# rhex.net
KiCad netlist of a schematic drawn in EAGLE
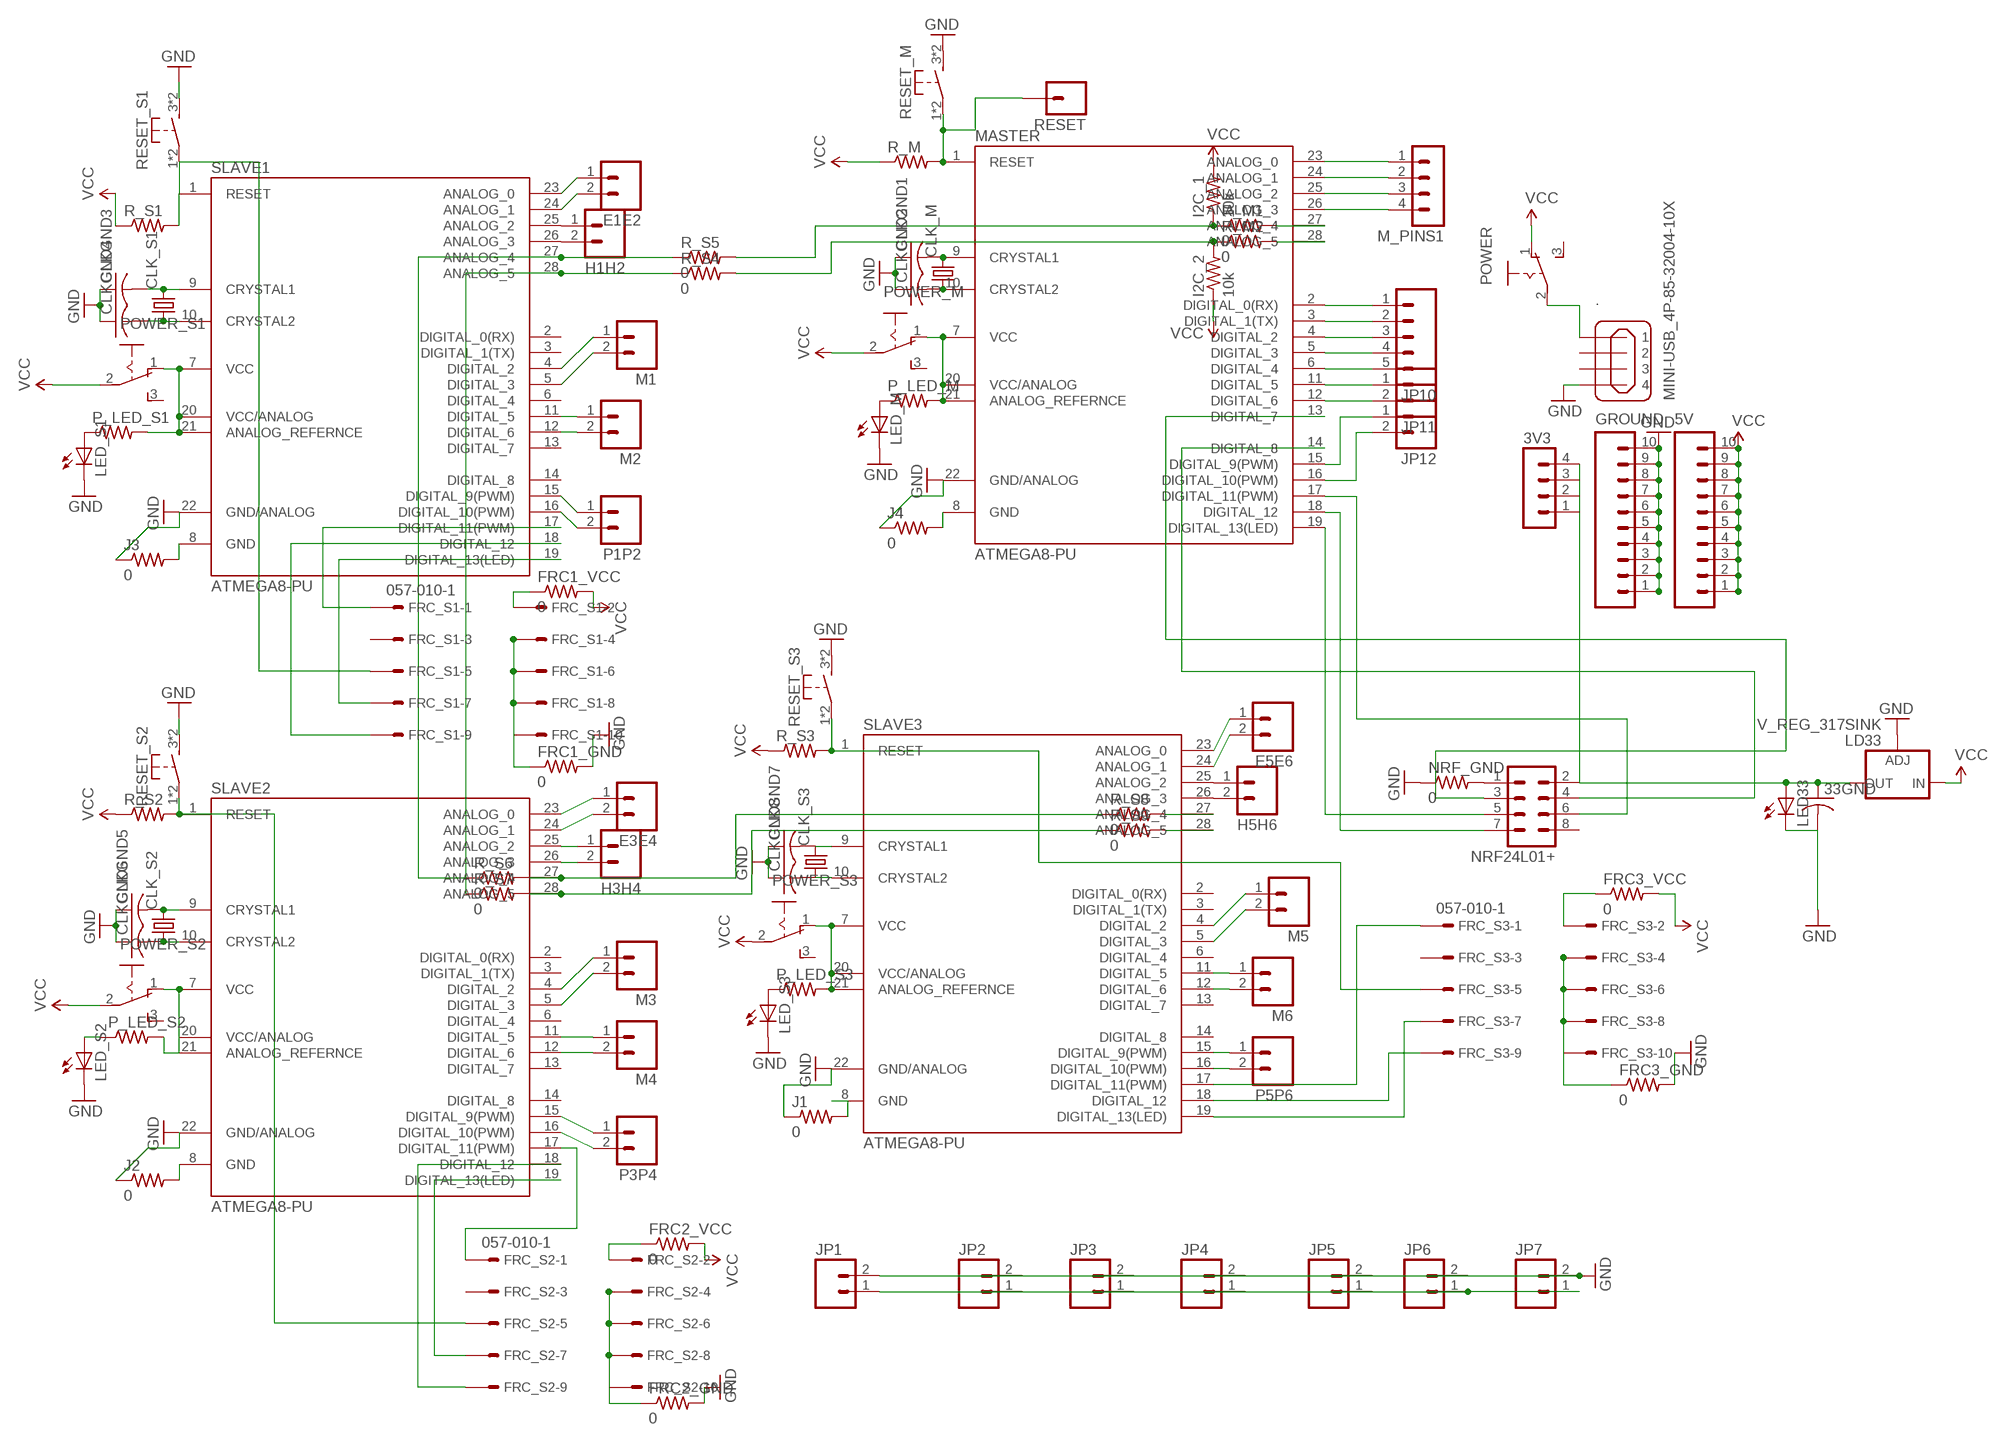
[diagram p0: schematic, sheet 1]

(export (version "E")
  (design (tool "Eeschema 10.0.6"))
  (components
    (comp (ref ".")
      (value "MINI-USB_4P-85-32004-10X")
      (footprint "eagle-import:85-32004-10X")
      (libsource (lib "eagle-import") (part "MINI-USB_4P-85-32004-10X"))
    )
    (comp (ref "3V3")
      (value "MA04-1")
      (footprint "eagle-import:MA04-1")
      (libsource (lib "eagle-import") (part "MA04-1"))
    )
    (comp (ref "5V")
      (value "M10SILK_FEMALE_PTH")
      (footprint "eagle-import:1X10")
      (libsource (lib "eagle-import") (part "M10SILK_FEMALE_PTH"))
    )
    (comp (ref "33GND")
      (value "C-US050-024X044")
      (footprint "eagle-import:C050-024X044")
      (libsource (lib "eagle-import") (part "C-US050-024X044"))
    )
    (comp (ref "CLKGND1")
      (value "C-US050-024X044")
      (footprint "eagle-import:C050-024X044")
      (libsource (lib "eagle-import") (part "C-US050-024X044"))
    )
    (comp (ref "CLKGND2")
      (value "C-US050-024X044")
      (footprint "eagle-import:C050-024X044")
      (libsource (lib "eagle-import") (part "C-US050-024X044"))
    )
    (comp (ref "CLKGND3")
      (value "C-US050-024X044")
      (footprint "eagle-import:C050-024X044")
      (libsource (lib "eagle-import") (part "C-US050-024X044"))
    )
    (comp (ref "CLKGND4")
      (value "C-US050-024X044")
      (footprint "eagle-import:C050-024X044")
      (libsource (lib "eagle-import") (part "C-US050-024X044"))
    )
    (comp (ref "CLKGND5")
      (value "C-US050-024X044")
      (footprint "eagle-import:C050-024X044")
      (libsource (lib "eagle-import") (part "C-US050-024X044"))
    )
    (comp (ref "CLKGND6")
      (value "C-US050-024X044")
      (footprint "eagle-import:C050-024X044")
      (libsource (lib "eagle-import") (part "C-US050-024X044"))
    )
    (comp (ref "CLKGND7")
      (value "C-US050-024X044")
      (footprint "eagle-import:C050-024X044")
      (libsource (lib "eagle-import") (part "C-US050-024X044"))
    )
    (comp (ref "CLKGND8")
      (value "C-US050-024X044")
      (footprint "eagle-import:C050-024X044")
      (libsource (lib "eagle-import") (part "C-US050-024X044"))
    )
    (comp (ref "CLK_M")
      (value "CRYSTALHC49U-V")
      (footprint "eagle-import:HC49U-V")
      (libsource (lib "eagle-import") (part "CRYSTALHC49U-V"))
    )
    (comp (ref "CLK_S1")
      (value "CRYSTALHC49U-V")
      (footprint "eagle-import:HC49U-V")
      (libsource (lib "eagle-import") (part "CRYSTALHC49U-V"))
    )
    (comp (ref "CLK_S2")
      (value "CRYSTALHC49U-V")
      (footprint "eagle-import:HC49U-V")
      (libsource (lib "eagle-import") (part "CRYSTALHC49U-V"))
    )
    (comp (ref "CLK_S3")
      (value "CRYSTALHC49U-V")
      (footprint "eagle-import:HC49U-V")
      (libsource (lib "eagle-import") (part "CRYSTALHC49U-V"))
    )
    (comp (ref "E1E2")
      (value "M02LOCK")
      (footprint "eagle-import:1X02_LOCK")
      (libsource (lib "eagle-import") (part "M02LOCK"))
    )
    (comp (ref "E3E4")
      (value "M02LOCK")
      (footprint "eagle-import:1X02_LOCK")
      (libsource (lib "eagle-import") (part "M02LOCK"))
    )
    (comp (ref "E5E6")
      (value "M02LOCK")
      (footprint "eagle-import:1X02_LOCK")
      (libsource (lib "eagle-import") (part "M02LOCK"))
    )
    (comp (ref "FRC1_GND")
      (value "0")
      (footprint "eagle-import:0411_15")
      (libsource (lib "eagle-import") (part "R-US_0411/15"))
    )
    (comp (ref "FRC1_VCC")
      (value "0")
      (footprint "eagle-import:0411_15")
      (libsource (lib "eagle-import") (part "R-US_0411/15"))
    )
    (comp (ref "FRC2_GND")
      (value "0")
      (footprint "eagle-import:0411_15")
      (libsource (lib "eagle-import") (part "R-US_0411/15"))
    )
    (comp (ref "FRC2_VCC")
      (value "0")
      (footprint "eagle-import:0411_15")
      (libsource (lib "eagle-import") (part "R-US_0411/15"))
    )
    (comp (ref "FRC3_GND")
      (value "0")
      (footprint "eagle-import:0411_15")
      (libsource (lib "eagle-import") (part "R-US_0411/15"))
    )
    (comp (ref "FRC3_VCC")
      (value "0")
      (footprint "eagle-import:0411_15")
      (libsource (lib "eagle-import") (part "R-US_0411/15"))
    )
    (comp (ref "FRC_S1")
      (value "057-010-1")
      (footprint "eagle-import:057-010-1")
      (libsource (lib "eagle-import") (part "057-010-1"))
    )
    (comp (ref "FRC_S2")
      (value "057-010-1")
      (footprint "eagle-import:057-010-1")
      (libsource (lib "eagle-import") (part "057-010-1"))
    )
    (comp (ref "FRC_S3")
      (value "057-010-1")
      (footprint "eagle-import:057-010-1")
      (libsource (lib "eagle-import") (part "057-010-1"))
    )
    (comp (ref "GROUND")
      (value "M10SILK_FEMALE_PTH")
      (footprint "eagle-import:1X10")
      (libsource (lib "eagle-import") (part "M10SILK_FEMALE_PTH"))
    )
    (comp (ref "H1H2")
      (value "M02LOCK")
      (footprint "eagle-import:1X02_LOCK")
      (libsource (lib "eagle-import") (part "M02LOCK"))
    )
    (comp (ref "H3H4")
      (value "M02LOCK")
      (footprint "eagle-import:1X02_LOCK")
      (libsource (lib "eagle-import") (part "M02LOCK"))
    )
    (comp (ref "H5H6")
      (value "M02LOCK")
      (footprint "eagle-import:1X02_LOCK")
      (libsource (lib "eagle-import") (part "M02LOCK"))
    )
    (comp (ref "I2C_1")
      (value "10k")
      (footprint "eagle-import:0411_15")
      (libsource (lib "eagle-import") (part "R-US_0411/15"))
    )
    (comp (ref "I2C_2")
      (value "10k")
      (footprint "eagle-import:0411_15")
      (libsource (lib "eagle-import") (part "R-US_0411/15"))
    )
    (comp (ref "J1")
      (value "0")
      (footprint "eagle-import:0411_15")
      (libsource (lib "eagle-import") (part "R-US_0411/15"))
    )
    (comp (ref "J2")
      (value "0")
      (footprint "eagle-import:0411_15")
      (libsource (lib "eagle-import") (part "R-US_0411/15"))
    )
    (comp (ref "J3")
      (value "0")
      (footprint "eagle-import:0411_15")
      (libsource (lib "eagle-import") (part "R-US_0411/15"))
    )
    (comp (ref "J4")
      (value "0")
      (footprint "eagle-import:0411_15")
      (libsource (lib "eagle-import") (part "R-US_0411/15"))
    )
    (comp (ref "JP1")
      (value "M023.5MM")
      (footprint "eagle-import:SCREWTERMINAL-3.5MM-2")
      (libsource (lib "eagle-import") (part "M023.5MM"))
    )
    (comp (ref "JP2")
      (value "M023.5MM")
      (footprint "eagle-import:SCREWTERMINAL-3.5MM-2")
      (libsource (lib "eagle-import") (part "M023.5MM"))
    )
    (comp (ref "JP3")
      (value "M023.5MM")
      (footprint "eagle-import:SCREWTERMINAL-3.5MM-2")
      (libsource (lib "eagle-import") (part "M023.5MM"))
    )
    (comp (ref "JP4")
      (value "M023.5MM")
      (footprint "eagle-import:SCREWTERMINAL-3.5MM-2")
      (libsource (lib "eagle-import") (part "M023.5MM"))
    )
    (comp (ref "JP5")
      (value "M023.5MM")
      (footprint "eagle-import:SCREWTERMINAL-3.5MM-2")
      (libsource (lib "eagle-import") (part "M023.5MM"))
    )
    (comp (ref "JP6")
      (value "M023.5MM")
      (footprint "eagle-import:SCREWTERMINAL-3.5MM-2")
      (libsource (lib "eagle-import") (part "M023.5MM"))
    )
    (comp (ref "JP7")
      (value "M023.5MM")
      (footprint "eagle-import:SCREWTERMINAL-3.5MM-2")
      (libsource (lib "eagle-import") (part "M023.5MM"))
    )
    (comp (ref "JP10")
      (value "M05PTH")
      (footprint "eagle-import:1X05")
      (libsource (lib "eagle-import") (part "M05PTH"))
    )
    (comp (ref "JP11")
      (value "M02PTH")
      (footprint "eagle-import:1X02")
      (libsource (lib "eagle-import") (part "M02PTH"))
    )
    (comp (ref "JP12")
      (value "M02PTH")
      (footprint "eagle-import:1X02")
      (libsource (lib "eagle-import") (part "M02PTH"))
    )
    (comp (ref "LD33")
      (value "V_REG_317SINK")
      (footprint "eagle-import:TO220-ADJ")
      (libsource (lib "eagle-import") (part "V_REG_317SINK"))
    )
    (comp (ref "LED33")
      (value "LED3MM")
      (footprint "eagle-import:LED3MM")
      (libsource (lib "eagle-import") (part "LED3MM"))
    )
    (comp (ref "LED_M")
      (value "LED3MM")
      (footprint "eagle-import:LED3MM")
      (libsource (lib "eagle-import") (part "led_LED3MM"))
    )
    (comp (ref "LED_S1")
      (value "LED3MM")
      (footprint "eagle-import:LED3MM")
      (libsource (lib "eagle-import") (part "led_LED3MM"))
    )
    (comp (ref "LED_S2")
      (value "LED3MM")
      (footprint "eagle-import:LED3MM")
      (libsource (lib "eagle-import") (part "led_LED3MM"))
    )
    (comp (ref "LED_S3")
      (value "LED3MM")
      (footprint "eagle-import:LED3MM")
      (libsource (lib "eagle-import") (part "led_LED3MM"))
    )
    (comp (ref "M1")
      (value "M02LOCK")
      (footprint "eagle-import:1X02_LOCK")
      (libsource (lib "eagle-import") (part "M02LOCK"))
    )
    (comp (ref "M2")
      (value "M02LOCK")
      (footprint "eagle-import:1X02_LOCK")
      (libsource (lib "eagle-import") (part "M02LOCK"))
    )
    (comp (ref "M3")
      (value "M02LOCK")
      (footprint "eagle-import:1X02_LOCK")
      (libsource (lib "eagle-import") (part "M02LOCK"))
    )
    (comp (ref "M4")
      (value "M02LOCK")
      (footprint "eagle-import:1X02_LOCK")
      (libsource (lib "eagle-import") (part "M02LOCK"))
    )
    (comp (ref "M5")
      (value "M02LOCK")
      (footprint "eagle-import:1X02_LOCK")
      (libsource (lib "eagle-import") (part "M02LOCK"))
    )
    (comp (ref "M6")
      (value "M02LOCK")
      (footprint "eagle-import:1X02_LOCK")
      (libsource (lib "eagle-import") (part "M02LOCK"))
    )
    (comp (ref "MASTER")
      (value "ATMEGA8-PU")
      (footprint "eagle-import:DIL28-3")
      (libsource (lib "eagle-import") (part "ATMEGA8-PU"))
    )
    (comp (ref "M_PINS1")
      (value "MA04-1")
      (footprint "eagle-import:MA04-1")
      (libsource (lib "eagle-import") (part "MA04-1"))
    )
    (comp (ref "NRF24L01+")
      (value "MA04-2")
      (footprint "eagle-import:MA04-2")
      (libsource (lib "eagle-import") (part "MA04-2"))
    )
    (comp (ref "NRF_GND")
      (value "0")
      (footprint "eagle-import:0411_15")
      (libsource (lib "eagle-import") (part "R-US_0411/15"))
    )
    (comp (ref "P1P2")
      (value "M02LOCK")
      (footprint "eagle-import:1X02_LOCK")
      (libsource (lib "eagle-import") (part "M02LOCK"))
    )
    (comp (ref "P3P4")
      (value "M02LOCK")
      (footprint "eagle-import:1X02_LOCK")
      (libsource (lib "eagle-import") (part "M02LOCK"))
    )
    (comp (ref "P5P6")
      (value "M02LOCK")
      (footprint "eagle-import:1X02_LOCK")
      (libsource (lib "eagle-import") (part "M02LOCK"))
    )
    (comp (ref "POWER")
      (value "M251")
      (footprint "eagle-import:M251")
      (libsource (lib "eagle-import") (part "M251"))
    )
    (comp (ref "POWER_M")
      (value "M251")
      (footprint "eagle-import:M251")
      (libsource (lib "eagle-import") (part "M251"))
    )
    (comp (ref "POWER_S1")
      (value "M251")
      (footprint "eagle-import:M251")
      (libsource (lib "eagle-import") (part "M251"))
    )
    (comp (ref "POWER_S2")
      (value "M251")
      (footprint "eagle-import:M251")
      (libsource (lib "eagle-import") (part "M251"))
    )
    (comp (ref "POWER_S3")
      (value "M251")
      (footprint "eagle-import:M251")
      (libsource (lib "eagle-import") (part "M251"))
    )
    (comp (ref "P_LED_M")
      (value "R-US_0411/15")
      (footprint "eagle-import:0411_15")
      (libsource (lib "eagle-import") (part "R-US_0411/15"))
    )
    (comp (ref "P_LED_S1")
      (value "R-US_0411/15")
      (footprint "eagle-import:0411_15")
      (libsource (lib "eagle-import") (part "R-US_0411/15"))
    )
    (comp (ref "P_LED_S2")
      (value "R-US_0411/15")
      (footprint "eagle-import:0411_15")
      (libsource (lib "eagle-import") (part "R-US_0411/15"))
    )
    (comp (ref "P_LED_S3")
      (value "R-US_0411/15")
      (footprint "eagle-import:0411_15")
      (libsource (lib "eagle-import") (part "R-US_0411/15"))
    )
    (comp (ref "RESET")
      (value "M01PTH")
      (footprint "eagle-import:1X01")
      (libsource (lib "eagle-import") (part "M01PTH"))
    )
    (comp (ref "RESET_M")
      (value "SW-TACTILE-6X6")
      (footprint "eagle-import:SW6X6")
      (libsource (lib "eagle-import") (part "SW-TACTILE-6X6"))
    )
    (comp (ref "RESET_S1")
      (value "SW-TACTILE-6X6")
      (footprint "eagle-import:SW6X6")
      (libsource (lib "eagle-import") (part "SW-TACTILE-6X6"))
    )
    (comp (ref "RESET_S2")
      (value "SW-TACTILE-6X6")
      (footprint "eagle-import:SW6X6")
      (libsource (lib "eagle-import") (part "SW-TACTILE-6X6"))
    )
    (comp (ref "RESET_S3")
      (value "SW-TACTILE-6X6")
      (footprint "eagle-import:SW6X6")
      (libsource (lib "eagle-import") (part "SW-TACTILE-6X6"))
    )
    (comp (ref "R_M")
      (value "R-US_0411/15")
      (footprint "eagle-import:0411_15")
      (libsource (lib "eagle-import") (part "R-US_0411/15"))
    )
    (comp (ref "R_M1")
      (value "0")
      (footprint "eagle-import:0411_15")
      (libsource (lib "eagle-import") (part "R-US_0411/15"))
    )
    (comp (ref "R_M2")
      (value "0")
      (footprint "eagle-import:0411_15")
      (libsource (lib "eagle-import") (part "R-US_0411/15"))
    )
    (comp (ref "R_S1")
      (value "R-US_0411/15")
      (footprint "eagle-import:0411_15")
      (libsource (lib "eagle-import") (part "R-US_0411/15"))
    )
    (comp (ref "R_S2")
      (value "R-US_0411/15")
      (footprint "eagle-import:0411_15")
      (libsource (lib "eagle-import") (part "R-US_0411/15"))
    )
    (comp (ref "R_S3")
      (value "R-US_0411/15")
      (footprint "eagle-import:0411_15")
      (libsource (lib "eagle-import") (part "R-US_0411/15"))
    )
    (comp (ref "R_S4")
      (value "0")
      (footprint "eagle-import:0411_15")
      (libsource (lib "eagle-import") (part "R-US_0411/15"))
    )
    (comp (ref "R_S5")
      (value "0")
      (footprint "eagle-import:0411_15")
      (libsource (lib "eagle-import") (part "R-US_0411/15"))
    )
    (comp (ref "R_S6")
      (value "0")
      (footprint "eagle-import:0411_15")
      (libsource (lib "eagle-import") (part "R-US_0411/15"))
    )
    (comp (ref "R_S7")
      (value "0")
      (footprint "eagle-import:0411_15")
      (libsource (lib "eagle-import") (part "R-US_0411/15"))
    )
    (comp (ref "R_S8")
      (value "0")
      (footprint "eagle-import:0411_15")
      (libsource (lib "eagle-import") (part "R-US_0411/15"))
    )
    (comp (ref "R_S9")
      (value "0")
      (footprint "eagle-import:0411_15")
      (libsource (lib "eagle-import") (part "R-US_0411/15"))
    )
    (comp (ref "SLAVE1")
      (value "ATMEGA8-PU")
      (footprint "eagle-import:DIL28-3")
      (libsource (lib "eagle-import") (part "ATMEGA8-PU"))
    )
    (comp (ref "SLAVE2")
      (value "ATMEGA8-PU")
      (footprint "eagle-import:DIL28-3")
      (libsource (lib "eagle-import") (part "ATMEGA8-PU"))
    )
    (comp (ref "SLAVE3")
      (value "ATMEGA8-PU")
      (footprint "eagle-import:DIL28-3")
      (libsource (lib "eagle-import") (part "ATMEGA8-PU"))
    )
  )
  (nets
    (net (code "1") (name "GND") (class "Default")
      (node (ref ".") (pin "4") (pinfunction "4_4") (pintype "passive"))
      (node (ref "33GND") (pin "2") (pinfunction "2_2") (pintype "passive"))
      (node (ref "CLKGND1") (pin "1") (pinfunction "1_1") (pintype "passive"))
      (node (ref "CLKGND2") (pin "1") (pinfunction "1_1") (pintype "passive"))
      (node (ref "CLKGND3") (pin "1") (pinfunction "1_1") (pintype "passive"))
      (node (ref "CLKGND4") (pin "1") (pinfunction "1_1") (pintype "passive"))
      (node (ref "CLKGND5") (pin "1") (pinfunction "1_1") (pintype "passive"))
      (node (ref "CLKGND6") (pin "1") (pinfunction "1_1") (pintype "passive"))
      (node (ref "CLKGND7") (pin "1") (pinfunction "1_1") (pintype "passive"))
      (node (ref "CLKGND8") (pin "1") (pinfunction "1_1") (pintype "passive"))
      (node (ref "FRC1_GND") (pin "2") (pinfunction "2_2") (pintype "passive"))
      (node (ref "FRC2_GND") (pin "2") (pinfunction "2_2") (pintype "passive"))
      (node (ref "FRC3_GND") (pin "2") (pinfunction "2_2") (pintype "passive"))
      (node (ref "GROUND") (pin "1") (pinfunction "1_1") (pintype "passive"))
      (node (ref "GROUND") (pin "10") (pinfunction "10_10") (pintype "passive"))
      (node (ref "GROUND") (pin "2") (pinfunction "2_2") (pintype "passive"))
      (node (ref "GROUND") (pin "3") (pinfunction "3_3") (pintype "passive"))
      (node (ref "GROUND") (pin "4") (pinfunction "4_4") (pintype "passive"))
      (node (ref "GROUND") (pin "5") (pinfunction "5_5") (pintype "passive"))
      (node (ref "GROUND") (pin "6") (pinfunction "6_6") (pintype "passive"))
      (node (ref "GROUND") (pin "7") (pinfunction "7_7") (pintype "passive"))
      (node (ref "GROUND") (pin "8") (pinfunction "8_8") (pintype "passive"))
      (node (ref "GROUND") (pin "9") (pinfunction "9_9") (pintype "passive"))
      (node (ref "J1") (pin "1") (pinfunction "1_1") (pintype "passive"))
      (node (ref "J2") (pin "1") (pinfunction "1_1") (pintype "passive"))
      (node (ref "J3") (pin "1") (pinfunction "1_1") (pintype "passive"))
      (node (ref "J4") (pin "1") (pinfunction "1_1") (pintype "passive"))
      (node (ref "JP1") (pin "2") (pinfunction "2_2") (pintype "passive"))
      (node (ref "JP2") (pin "2") (pinfunction "2_2") (pintype "passive"))
      (node (ref "JP3") (pin "2") (pinfunction "2_2") (pintype "passive"))
      (node (ref "JP4") (pin "2") (pinfunction "2_2") (pintype "passive"))
      (node (ref "JP5") (pin "2") (pinfunction "2_2") (pintype "passive"))
      (node (ref "JP6") (pin "2") (pinfunction "2_2") (pintype "passive"))
      (node (ref "JP7") (pin "2") (pinfunction "2_2") (pintype "passive"))
      (node (ref "LD33") (pin "ADJ") (pinfunction "ADJ_ADJ") (pintype "input"))
      (node (ref "LED33") (pin "K") (pinfunction "C_K") (pintype "passive"))
      (node (ref "LED_M") (pin "K") (pinfunction "C_K") (pintype "passive"))
      (node (ref "LED_S1") (pin "K") (pinfunction "C_K") (pintype "passive"))
      (node (ref "LED_S2") (pin "K") (pinfunction "C_K") (pintype "passive"))
      (node (ref "LED_S3") (pin "K") (pinfunction "C_K") (pintype "passive"))
      (node (ref "MASTER") (pin "22") (pinfunction "GND/ANALOG_22") (pintype "power_in"))
      (node (ref "NRF_GND") (pin "1") (pinfunction "1_1") (pintype "passive"))
      (node (ref "RESET_M") (pin "3") (pinfunction "S1_3") (pintype "passive"))
      (node (ref "RESET_M") (pin "4") (pinfunction "S1_4") (pintype "passive"))
      (node (ref "RESET_S1") (pin "3") (pinfunction "S1_3") (pintype "passive"))
      (node (ref "RESET_S1") (pin "4") (pinfunction "S1_4") (pintype "passive"))
      (node (ref "RESET_S2") (pin "3") (pinfunction "S1_3") (pintype "passive"))
      (node (ref "RESET_S2") (pin "4") (pinfunction "S1_4") (pintype "passive"))
      (node (ref "RESET_S3") (pin "3") (pinfunction "S1_3") (pintype "passive"))
      (node (ref "RESET_S3") (pin "4") (pinfunction "S1_4") (pintype "passive"))
      (node (ref "SLAVE1") (pin "22") (pinfunction "GND/ANALOG_22") (pintype "power_in"))
      (node (ref "SLAVE2") (pin "22") (pinfunction "GND/ANALOG_22") (pintype "power_in"))
      (node (ref "SLAVE3") (pin "22") (pinfunction "GND/ANALOG_22") (pintype "power_in"))
    )
    (net (code "2") (name "Net-(33GND-Pad1)") (class "Default")
      (node (ref "33GND") (pin "1") (pinfunction "1_1") (pintype "passive"))
      (node (ref "3V3") (pin "1") (pinfunction "1_1") (pintype "passive"))
      (node (ref "3V3") (pin "4") (pinfunction "4_4") (pintype "passive"))
      (node (ref "LD33") (pin "OUT") (pinfunction "OUT_OUT") (pintype "output"))
      (node (ref "LED33") (pin "A") (pinfunction "A_A") (pintype "passive"))
      (node (ref "NRF24L01+") (pin "2") (pinfunction "2_2") (pintype "passive"))
    )
    (net (code "3") (name "Net-(FRC_S1A-S)") (class "Default")
      (node (ref "FRC_S1") (pin "1") (pinfunction "S_1") (pintype "passive"))
      (node (ref "SLAVE1") (pin "17") (pinfunction "DIGITAL_11(PWM)_17") (pintype "bidirectional"))
    )
    (net (code "4") (name "Net-(FRC_S1B-S)") (class "Default")
      (node (ref "FRC1_GND") (pin "1") (pinfunction "1_1") (pintype "passive"))
      (node (ref "FRC_S1") (pin "10") (pinfunction "S_10") (pintype "passive"))
      (node (ref "FRC_S1") (pin "4") (pinfunction "S_4") (pintype "passive"))
      (node (ref "FRC_S1") (pin "6") (pinfunction "S_6") (pintype "passive"))
      (node (ref "FRC_S1") (pin "8") (pinfunction "S_8") (pintype "passive"))
    )
    (net (code "5") (name "Net-(FRC_S1C-S)") (class "Default")
      (node (ref "FRC1_VCC") (pin "1") (pinfunction "1_1") (pintype "passive"))
      (node (ref "FRC_S1") (pin "2") (pinfunction "S_2") (pintype "passive"))
    )
    (net (code "6") (name "Net-(FRC_S1F-S)") (class "Default")
      (node (ref "FRC_S1") (pin "5") (pinfunction "S_5") (pintype "passive"))
      (node (ref "RESET_S1") (pin "1") (pinfunction "P1_1") (pintype "passive"))
      (node (ref "RESET_S1") (pin "2") (pinfunction "P1_2") (pintype "passive"))
      (node (ref "R_S1") (pin "2") (pinfunction "2_2") (pintype "passive"))
      (node (ref "SLAVE1") (pin "1") (pinfunction "RESET_1") (pintype "bidirectional"))
    )
    (net (code "7") (name "Net-(FRC_S1H-S)") (class "Default")
      (node (ref "FRC_S1") (pin "7") (pinfunction "S_7") (pintype "passive"))
      (node (ref "SLAVE1") (pin "19") (pinfunction "DIGITAL_13(LED)_19") (pintype "bidirectional"))
    )
    (net (code "8") (name "Net-(FRC_S1J-S)") (class "Default")
      (node (ref "FRC_S1") (pin "9") (pinfunction "S_9") (pintype "passive"))
      (node (ref "SLAVE1") (pin "18") (pinfunction "DIGITAL_12_18") (pintype "bidirectional"))
    )
    (net (code "9") (name "Net-(FRC_S2A-S)") (class "Default")
      (node (ref "FRC_S2") (pin "1") (pinfunction "S_1") (pintype "passive"))
      (node (ref "SLAVE2") (pin "17") (pinfunction "DIGITAL_11(PWM)_17") (pintype "bidirectional"))
    )
    (net (code "10") (name "Net-(FRC_S2B-S)") (class "Default")
      (node (ref "FRC2_GND") (pin "1") (pinfunction "1_1") (pintype "passive"))
      (node (ref "FRC_S2") (pin "10") (pinfunction "S_10") (pintype "passive"))
      (node (ref "FRC_S2") (pin "4") (pinfunction "S_4") (pintype "passive"))
      (node (ref "FRC_S2") (pin "6") (pinfunction "S_6") (pintype "passive"))
      (node (ref "FRC_S2") (pin "8") (pinfunction "S_8") (pintype "passive"))
    )
    (net (code "11") (name "Net-(FRC_S2C-S)") (class "Default")
      (node (ref "FRC2_VCC") (pin "1") (pinfunction "1_1") (pintype "passive"))
      (node (ref "FRC_S2") (pin "2") (pinfunction "S_2") (pintype "passive"))
    )
    (net (code "12") (name "Net-(FRC_S2F-S)") (class "Default")
      (node (ref "FRC_S2") (pin "5") (pinfunction "S_5") (pintype "passive"))
      (node (ref "RESET_S2") (pin "1") (pinfunction "P1_1") (pintype "passive"))
      (node (ref "RESET_S2") (pin "2") (pinfunction "P1_2") (pintype "passive"))
      (node (ref "R_S2") (pin "2") (pinfunction "2_2") (pintype "passive"))
      (node (ref "SLAVE2") (pin "1") (pinfunction "RESET_1") (pintype "bidirectional"))
    )
    (net (code "13") (name "Net-(FRC_S2H-S)") (class "Default")
      (node (ref "FRC_S2") (pin "7") (pinfunction "S_7") (pintype "passive"))
      (node (ref "SLAVE2") (pin "19") (pinfunction "DIGITAL_13(LED)_19") (pintype "bidirectional"))
    )
    (net (code "14") (name "Net-(FRC_S2J-S)") (class "Default")
      (node (ref "FRC_S2") (pin "9") (pinfunction "S_9") (pintype "passive"))
      (node (ref "SLAVE2") (pin "18") (pinfunction "DIGITAL_12_18") (pintype "bidirectional"))
    )
    (net (code "15") (name "Net-(FRC_S3A-S)") (class "Default")
      (node (ref "FRC_S3") (pin "1") (pinfunction "S_1") (pintype "passive"))
      (node (ref "SLAVE3") (pin "17") (pinfunction "DIGITAL_11(PWM)_17") (pintype "bidirectional"))
    )
    (net (code "16") (name "Net-(FRC_S3B-S)") (class "Default")
      (node (ref "FRC3_GND") (pin "1") (pinfunction "1_1") (pintype "passive"))
      (node (ref "FRC_S3") (pin "10") (pinfunction "S_10") (pintype "passive"))
      (node (ref "FRC_S3") (pin "4") (pinfunction "S_4") (pintype "passive"))
      (node (ref "FRC_S3") (pin "6") (pinfunction "S_6") (pintype "passive"))
      (node (ref "FRC_S3") (pin "8") (pinfunction "S_8") (pintype "passive"))
    )
    (net (code "17") (name "Net-(FRC_S3C-S)") (class "Default")
      (node (ref "FRC3_VCC") (pin "1") (pinfunction "1_1") (pintype "passive"))
      (node (ref "FRC_S3") (pin "2") (pinfunction "S_2") (pintype "passive"))
    )
    (net (code "18") (name "Net-(FRC_S3F-S)") (class "Default")
      (node (ref "FRC_S3") (pin "5") (pinfunction "S_5") (pintype "passive"))
      (node (ref "RESET_S3") (pin "1") (pinfunction "P1_1") (pintype "passive"))
      (node (ref "RESET_S3") (pin "2") (pinfunction "P1_2") (pintype "passive"))
      (node (ref "R_S3") (pin "2") (pinfunction "2_2") (pintype "passive"))
      (node (ref "SLAVE3") (pin "1") (pinfunction "RESET_1") (pintype "bidirectional"))
    )
    (net (code "19") (name "Net-(FRC_S3H-S)") (class "Default")
      (node (ref "FRC_S3") (pin "7") (pinfunction "S_7") (pintype "passive"))
      (node (ref "SLAVE3") (pin "19") (pinfunction "DIGITAL_13(LED)_19") (pintype "bidirectional"))
    )
    (net (code "20") (name "Net-(FRC_S3J-S)") (class "Default")
      (node (ref "FRC_S3") (pin "9") (pinfunction "S_9") (pintype "passive"))
      (node (ref "SLAVE3") (pin "18") (pinfunction "DIGITAL_12_18") (pintype "bidirectional"))
    )
    (net (code "21") (name "Net-(I2C_1-Pad1)") (class "Default")
      (node (ref "I2C_1") (pin "1") (pinfunction "1_1") (pintype "passive"))
      (node (ref "R_M1") (pin "1") (pinfunction "1_1") (pintype "passive"))
      (node (ref "R_S5") (pin "2") (pinfunction "2_2") (pintype "passive"))
    )
    (net (code "22") (name "Net-(I2C_2-Pad2)") (class "Default")
      (node (ref "I2C_2") (pin "2") (pinfunction "2_2") (pintype "passive"))
      (node (ref "R_M2") (pin "1") (pinfunction "1_1") (pintype "passive"))
      (node (ref "R_S4") (pin "2") (pinfunction "2_2") (pintype "passive"))
    )
    (net (code "23") (name "Net-(JP1-Pad1)") (class "Default")
      (node (ref "JP1") (pin "1") (pinfunction "1_1") (pintype "passive"))
      (node (ref "JP2") (pin "1") (pinfunction "1_1") (pintype "passive"))
      (node (ref "JP3") (pin "1") (pinfunction "1_1") (pintype "passive"))
      (node (ref "JP4") (pin "1") (pinfunction "1_1") (pintype "passive"))
      (node (ref "JP5") (pin "1") (pinfunction "1_1") (pintype "passive"))
      (node (ref "JP6") (pin "1") (pinfunction "1_1") (pintype "passive"))
      (node (ref "JP7") (pin "1") (pinfunction "1_1") (pintype "passive"))
    )
    (net (code "24") (name "Net-(LED_M-PadA)") (class "Default")
      (node (ref "LED_M") (pin "A") (pinfunction "A_A") (pintype "passive"))
      (node (ref "P_LED_M") (pin "1") (pinfunction "1_1") (pintype "passive"))
    )
    (net (code "25") (name "Net-(LED_S1-PadA)") (class "Default")
      (node (ref "LED_S1") (pin "A") (pinfunction "A_A") (pintype "passive"))
      (node (ref "P_LED_S1") (pin "1") (pinfunction "1_1") (pintype "passive"))
    )
    (net (code "26") (name "Net-(LED_S2-PadA)") (class "Default")
      (node (ref "LED_S2") (pin "A") (pinfunction "A_A") (pintype "passive"))
      (node (ref "P_LED_S2") (pin "1") (pinfunction "1_1") (pintype "passive"))
    )
    (net (code "27") (name "Net-(LED_S3-PadA)") (class "Default")
      (node (ref "LED_S3") (pin "A") (pinfunction "A_A") (pintype "passive"))
      (node (ref "P_LED_S3") (pin "1") (pinfunction "1_1") (pintype "passive"))
    )
    (net (code "28") (name "Net-(MASTER-ANALOG_0)") (class "Default")
      (node (ref "MASTER") (pin "23") (pinfunction "ANALOG_0_23") (pintype "bidirectional"))
      (node (ref "M_PINS1") (pin "1") (pinfunction "1_1") (pintype "passive"))
    )
    (net (code "29") (name "Net-(MASTER-ANALOG_1)") (class "Default")
      (node (ref "MASTER") (pin "24") (pinfunction "ANALOG_1_24") (pintype "bidirectional"))
      (node (ref "M_PINS1") (pin "2") (pinfunction "2_2") (pintype "passive"))
    )
    (net (code "30") (name "Net-(MASTER-ANALOG_2)") (class "Default")
      (node (ref "MASTER") (pin "25") (pinfunction "ANALOG_2_25") (pintype "bidirectional"))
      (node (ref "M_PINS1") (pin "3") (pinfunction "3_3") (pintype "passive"))
    )
    (net (code "31") (name "Net-(MASTER-ANALOG_3)") (class "Default")
      (node (ref "MASTER") (pin "26") (pinfunction "ANALOG_3_26") (pintype "bidirectional"))
      (node (ref "M_PINS1") (pin "4") (pinfunction "4_4") (pintype "passive"))
    )
    (net (code "32") (name "Net-(MASTER-ANALOG_4)") (class "Default")
      (node (ref "MASTER") (pin "27") (pinfunction "ANALOG_4_27") (pintype "bidirectional"))
      (node (ref "R_M1") (pin "2") (pinfunction "2_2") (pintype "passive"))
    )
    (net (code "33") (name "Net-(MASTER-ANALOG_5)") (class "Default")
      (node (ref "MASTER") (pin "28") (pinfunction "ANALOG_5_28") (pintype "bidirectional"))
      (node (ref "R_M2") (pin "2") (pinfunction "2_2") (pintype "passive"))
    )
    (net (code "34") (name "Net-(MASTER-ANALOG_REFERNCE)") (class "Default")
      (node (ref "MASTER") (pin "20") (pinfunction "VCC/ANALOG_20") (pintype "passive"))
      (node (ref "MASTER") (pin "21") (pinfunction "ANALOG_REFERNCE_21") (pintype "passive"))
      (node (ref "MASTER") (pin "7") (pinfunction "VCC_7") (pintype "power_in"))
      (node (ref "POWER_M") (pin "1") (pinfunction "O_1") (pintype "passive"))
      (node (ref "P_LED_M") (pin "2") (pinfunction "2_2") (pintype "passive"))
    )
    (net (code "35") (name "Net-(MASTER-CRYSTAL1)") (class "Default")
      (node (ref "CLKGND1") (pin "2") (pinfunction "2_2") (pintype "passive"))
      (node (ref "CLK_M") (pin "2") (pinfunction "2_2") (pintype "passive"))
      (node (ref "MASTER") (pin "9") (pinfunction "CRYSTAL1_9") (pintype "bidirectional"))
    )
    (net (code "36") (name "Net-(MASTER-CRYSTAL2)") (class "Default")
      (node (ref "CLKGND2") (pin "2") (pinfunction "2_2") (pintype "passive"))
      (node (ref "CLK_M") (pin "1") (pinfunction "1_1") (pintype "passive"))
      (node (ref "MASTER") (pin "10") (pinfunction "CRYSTAL2_10") (pintype "bidirectional"))
    )
    (net (code "37") (name "Net-(MASTER-DIGITAL_0(RX))") (class "Default")
      (node (ref "JP10") (pin "1") (pinfunction "1_1") (pintype "passive"))
      (node (ref "MASTER") (pin "2") (pinfunction "DIGITAL_0(RX)_2") (pintype "bidirectional"))
    )
    (net (code "38") (name "Net-(MASTER-DIGITAL_1(TX))") (class "Default")
      (node (ref "JP10") (pin "2") (pinfunction "2_2") (pintype "passive"))
      (node (ref "MASTER") (pin "3") (pinfunction "DIGITAL_1(TX)_3") (pintype "bidirectional"))
    )
    (net (code "39") (name "Net-(MASTER-DIGITAL_2)") (class "Default")
      (node (ref "JP10") (pin "3") (pinfunction "3_3") (pintype "passive"))
      (node (ref "MASTER") (pin "4") (pinfunction "DIGITAL_2_4") (pintype "bidirectional"))
    )
    (net (code "40") (name "Net-(MASTER-DIGITAL_3)") (class "Default")
      (node (ref "JP10") (pin "4") (pinfunction "4_4") (pintype "passive"))
      (node (ref "MASTER") (pin "5") (pinfunction "DIGITAL_3_5") (pintype "bidirectional"))
    )
    (net (code "41") (name "Net-(MASTER-DIGITAL_4)") (class "Default")
      (node (ref "JP10") (pin "5") (pinfunction "5_5") (pintype "passive"))
      (node (ref "MASTER") (pin "6") (pinfunction "DIGITAL_4_6") (pintype "bidirectional"))
    )
    (net (code "42") (name "Net-(MASTER-DIGITAL_5)") (class "Default")
      (node (ref "JP11") (pin "1") (pinfunction "1_1") (pintype "passive"))
      (node (ref "MASTER") (pin "11") (pinfunction "DIGITAL_5_11") (pintype "bidirectional"))
    )
    (net (code "43") (name "Net-(MASTER-DIGITAL_6)") (class "Default")
      (node (ref "JP11") (pin "2") (pinfunction "2_2") (pintype "passive"))
      (node (ref "MASTER") (pin "12") (pinfunction "DIGITAL_6_12") (pintype "bidirectional"))
    )
    (net (code "44") (name "Net-(MASTER-DIGITAL_7)") (class "Default")
      (node (ref "MASTER") (pin "13") (pinfunction "DIGITAL_7_13") (pintype "bidirectional"))
      (node (ref "NRF24L01+") (pin "3") (pinfunction "3_3") (pintype "passive"))
    )
    (net (code "45") (name "Net-(MASTER-DIGITAL_8)") (class "Default")
      (node (ref "MASTER") (pin "14") (pinfunction "DIGITAL_8_14") (pintype "bidirectional"))
      (node (ref "NRF24L01+") (pin "4") (pinfunction "4_4") (pintype "passive"))
    )
    (net (code "46") (name "Net-(MASTER-DIGITAL_9(PWM))") (class "Default")
      (node (ref "JP12") (pin "1") (pinfunction "1_1") (pintype "passive"))
      (node (ref "MASTER") (pin "15") (pinfunction "DIGITAL_9(PWM)_15") (pintype "bidirectional"))
    )
    (net (code "47") (name "Net-(MASTER-DIGITAL_10(PWM))") (class "Default")
      (node (ref "JP12") (pin "2") (pinfunction "2_2") (pintype "passive"))
      (node (ref "MASTER") (pin "16") (pinfunction "DIGITAL_10(PWM)_16") (pintype "bidirectional"))
    )
    (net (code "48") (name "Net-(MASTER-DIGITAL_11(PWM))") (class "Default")
      (node (ref "MASTER") (pin "17") (pinfunction "DIGITAL_11(PWM)_17") (pintype "bidirectional"))
      (node (ref "NRF24L01+") (pin "6") (pinfunction "6_6") (pintype "passive"))
    )
    (net (code "49") (name "Net-(MASTER-DIGITAL_12)") (class "Default")
      (node (ref "MASTER") (pin "18") (pinfunction "DIGITAL_12_18") (pintype "bidirectional"))
      (node (ref "NRF24L01+") (pin "7") (pinfunction "7_7") (pintype "passive"))
    )
    (net (code "50") (name "Net-(MASTER-DIGITAL_13(LED))") (class "Default")
      (node (ref "MASTER") (pin "19") (pinfunction "DIGITAL_13(LED)_19") (pintype "bidirectional"))
      (node (ref "NRF24L01+") (pin "5") (pinfunction "5_5") (pintype "passive"))
    )
    (net (code "51") (name "Net-(MASTER-GND)") (class "Default")
      (node (ref "J4") (pin "2") (pinfunction "2_2") (pintype "passive"))
      (node (ref "MASTER") (pin "8") (pinfunction "GND_8") (pintype "power_in"))
    )
    (net (code "52") (name "Net-(MASTER-RESET)") (class "Default")
      (node (ref "MASTER") (pin "1") (pinfunction "RESET_1") (pintype "bidirectional"))
      (node (ref "RESET") (pin "1") (pinfunction "1_1") (pintype "passive"))
      (node (ref "RESET_M") (pin "1") (pinfunction "P1_1") (pintype "passive"))
      (node (ref "RESET_M") (pin "2") (pinfunction "P1_2") (pintype "passive"))
      (node (ref "R_M") (pin "2") (pinfunction "2_2") (pintype "passive"))
    )
    (net (code "53") (name "Net-(NRF24L01+-Pad1)") (class "Default")
      (node (ref "NRF24L01+") (pin "1") (pinfunction "1_1") (pintype "passive"))
      (node (ref "NRF_GND") (pin "2") (pinfunction "2_2") (pintype "passive"))
    )
    (net (code "54") (name "Net-(POWER-P)") (class "Default")
      (node (ref ".") (pin "1") (pinfunction "1_1") (pintype "passive"))
      (node (ref "POWER") (pin "2") (pinfunction "P_2") (pintype "passive"))
    )
    (net (code "55") (name "Net-(POWER_S1-O)") (class "Default")
      (node (ref "POWER_S1") (pin "1") (pinfunction "O_1") (pintype "passive"))
      (node (ref "P_LED_S1") (pin "2") (pinfunction "2_2") (pintype "passive"))
      (node (ref "SLAVE1") (pin "20") (pinfunction "VCC/ANALOG_20") (pintype "passive"))
      (node (ref "SLAVE1") (pin "21") (pinfunction "ANALOG_REFERNCE_21") (pintype "passive"))
      (node (ref "SLAVE1") (pin "7") (pinfunction "VCC_7") (pintype "power_in"))
    )
    (net (code "56") (name "Net-(POWER_S2-O)") (class "Default")
      (node (ref "POWER_S2") (pin "1") (pinfunction "O_1") (pintype "passive"))
      (node (ref "P_LED_S2") (pin "2") (pinfunction "2_2") (pintype "passive"))
      (node (ref "SLAVE2") (pin "20") (pinfunction "VCC/ANALOG_20") (pintype "passive"))
      (node (ref "SLAVE2") (pin "21") (pinfunction "ANALOG_REFERNCE_21") (pintype "passive"))
      (node (ref "SLAVE2") (pin "7") (pinfunction "VCC_7") (pintype "power_in"))
    )
    (net (code "57") (name "Net-(POWER_S3-O)") (class "Default")
      (node (ref "POWER_S3") (pin "1") (pinfunction "O_1") (pintype "passive"))
      (node (ref "P_LED_S3") (pin "2") (pinfunction "2_2") (pintype "passive"))
      (node (ref "SLAVE3") (pin "20") (pinfunction "VCC/ANALOG_20") (pintype "passive"))
      (node (ref "SLAVE3") (pin "21") (pinfunction "ANALOG_REFERNCE_21") (pintype "passive"))
      (node (ref "SLAVE3") (pin "7") (pinfunction "VCC_7") (pintype "power_in"))
    )
    (net (code "58") (name "Net-(SLAVE1-ANALOG_0)") (class "Default")
      (node (ref "E1E2") (pin "1") (pinfunction "1_1") (pintype "passive"))
      (node (ref "SLAVE1") (pin "23") (pinfunction "ANALOG_0_23") (pintype "bidirectional"))
    )
    (net (code "59") (name "Net-(SLAVE1-ANALOG_1)") (class "Default")
      (node (ref "E1E2") (pin "2") (pinfunction "2_2") (pintype "passive"))
      (node (ref "SLAVE1") (pin "24") (pinfunction "ANALOG_1_24") (pintype "bidirectional"))
    )
    (net (code "60") (name "Net-(SLAVE1-ANALOG_2)") (class "Default")
      (node (ref "H1H2") (pin "1") (pinfunction "1_1") (pintype "passive"))
      (node (ref "SLAVE1") (pin "25") (pinfunction "ANALOG_2_25") (pintype "bidirectional"))
    )
    (net (code "61") (name "Net-(SLAVE1-ANALOG_3)") (class "Default")
      (node (ref "H1H2") (pin "2") (pinfunction "2_2") (pintype "passive"))
      (node (ref "SLAVE1") (pin "26") (pinfunction "ANALOG_3_26") (pintype "bidirectional"))
    )
    (net (code "62") (name "Net-(SLAVE1-ANALOG_4)") (class "Default")
      (node (ref "R_S5") (pin "1") (pinfunction "1_1") (pintype "passive"))
      (node (ref "R_S6") (pin "1") (pinfunction "1_1") (pintype "passive"))
      (node (ref "SLAVE1") (pin "27") (pinfunction "ANALOG_4_27") (pintype "bidirectional"))
    )
    (net (code "63") (name "Net-(SLAVE1-ANALOG_5)") (class "Default")
      (node (ref "R_S4") (pin "1") (pinfunction "1_1") (pintype "passive"))
      (node (ref "R_S7") (pin "1") (pinfunction "1_1") (pintype "passive"))
      (node (ref "SLAVE1") (pin "28") (pinfunction "ANALOG_5_28") (pintype "bidirectional"))
    )
    (net (code "64") (name "Net-(SLAVE1-CRYSTAL1)") (class "Default")
      (node (ref "CLKGND3") (pin "2") (pinfunction "2_2") (pintype "passive"))
      (node (ref "CLK_S1") (pin "2") (pinfunction "2_2") (pintype "passive"))
      (node (ref "SLAVE1") (pin "9") (pinfunction "CRYSTAL1_9") (pintype "bidirectional"))
    )
    (net (code "65") (name "Net-(SLAVE1-CRYSTAL2)") (class "Default")
      (node (ref "CLKGND4") (pin "2") (pinfunction "2_2") (pintype "passive"))
      (node (ref "CLK_S1") (pin "1") (pinfunction "1_1") (pintype "passive"))
      (node (ref "SLAVE1") (pin "10") (pinfunction "CRYSTAL2_10") (pintype "bidirectional"))
    )
    (net (code "66") (name "Net-(SLAVE1-DIGITAL_2)") (class "Default")
      (node (ref "M1") (pin "1") (pinfunction "1_1") (pintype "passive"))
      (node (ref "SLAVE1") (pin "4") (pinfunction "DIGITAL_2_4") (pintype "bidirectional"))
    )
    (net (code "67") (name "Net-(SLAVE1-DIGITAL_3)") (class "Default")
      (node (ref "M1") (pin "2") (pinfunction "2_2") (pintype "passive"))
      (node (ref "SLAVE1") (pin "5") (pinfunction "DIGITAL_3_5") (pintype "bidirectional"))
    )
    (net (code "68") (name "Net-(SLAVE1-DIGITAL_5)") (class "Default")
      (node (ref "M2") (pin "1") (pinfunction "1_1") (pintype "passive"))
      (node (ref "SLAVE1") (pin "11") (pinfunction "DIGITAL_5_11") (pintype "bidirectional"))
    )
    (net (code "69") (name "Net-(SLAVE1-DIGITAL_6)") (class "Default")
      (node (ref "M2") (pin "2") (pinfunction "2_2") (pintype "passive"))
      (node (ref "SLAVE1") (pin "12") (pinfunction "DIGITAL_6_12") (pintype "bidirectional"))
    )
    (net (code "70") (name "Net-(SLAVE1-DIGITAL_9(PWM))") (class "Default")
      (node (ref "P1P2") (pin "1") (pinfunction "1_1") (pintype "passive"))
      (node (ref "SLAVE1") (pin "15") (pinfunction "DIGITAL_9(PWM)_15") (pintype "bidirectional"))
    )
    (net (code "71") (name "Net-(SLAVE1-DIGITAL_10(PWM))") (class "Default")
      (node (ref "P1P2") (pin "2") (pinfunction "2_2") (pintype "passive"))
      (node (ref "SLAVE1") (pin "16") (pinfunction "DIGITAL_10(PWM)_16") (pintype "bidirectional"))
    )
    (net (code "72") (name "Net-(SLAVE1-GND)") (class "Default")
      (node (ref "J3") (pin "2") (pinfunction "2_2") (pintype "passive"))
      (node (ref "SLAVE1") (pin "8") (pinfunction "GND_8") (pintype "power_in"))
    )
    (net (code "73") (name "Net-(SLAVE2-ANALOG_0)") (class "Default")
      (node (ref "E3E4") (pin "1") (pinfunction "1_1") (pintype "passive"))
      (node (ref "SLAVE2") (pin "23") (pinfunction "ANALOG_0_23") (pintype "bidirectional"))
    )
    (net (code "74") (name "Net-(SLAVE2-ANALOG_1)") (class "Default")
      (node (ref "E3E4") (pin "2") (pinfunction "2_2") (pintype "passive"))
      (node (ref "SLAVE2") (pin "24") (pinfunction "ANALOG_1_24") (pintype "bidirectional"))
    )
    (net (code "75") (name "Net-(SLAVE2-ANALOG_2)") (class "Default")
      (node (ref "H3H4") (pin "1") (pinfunction "1_1") (pintype "passive"))
      (node (ref "SLAVE2") (pin "25") (pinfunction "ANALOG_2_25") (pintype "bidirectional"))
    )
    (net (code "76") (name "Net-(SLAVE2-ANALOG_3)") (class "Default")
      (node (ref "H3H4") (pin "2") (pinfunction "2_2") (pintype "passive"))
      (node (ref "SLAVE2") (pin "26") (pinfunction "ANALOG_3_26") (pintype "bidirectional"))
    )
    (net (code "77") (name "Net-(SLAVE2-ANALOG_4)") (class "Default")
      (node (ref "R_S6") (pin "2") (pinfunction "2_2") (pintype "passive"))
      (node (ref "R_S8") (pin "1") (pinfunction "1_1") (pintype "passive"))
      (node (ref "SLAVE2") (pin "27") (pinfunction "ANALOG_4_27") (pintype "bidirectional"))
    )
    (net (code "78") (name "Net-(SLAVE2-ANALOG_5)") (class "Default")
      (node (ref "R_S7") (pin "2") (pinfunction "2_2") (pintype "passive"))
      (node (ref "R_S9") (pin "1") (pinfunction "1_1") (pintype "passive"))
      (node (ref "SLAVE2") (pin "28") (pinfunction "ANALOG_5_28") (pintype "bidirectional"))
    )
    (net (code "79") (name "Net-(SLAVE2-CRYSTAL1)") (class "Default")
      (node (ref "CLKGND5") (pin "2") (pinfunction "2_2") (pintype "passive"))
      (node (ref "CLK_S2") (pin "2") (pinfunction "2_2") (pintype "passive"))
      (node (ref "SLAVE2") (pin "9") (pinfunction "CRYSTAL1_9") (pintype "bidirectional"))
    )
    (net (code "80") (name "Net-(SLAVE2-CRYSTAL2)") (class "Default")
      (node (ref "CLKGND6") (pin "2") (pinfunction "2_2") (pintype "passive"))
      (node (ref "CLK_S2") (pin "1") (pinfunction "1_1") (pintype "passive"))
      (node (ref "SLAVE2") (pin "10") (pinfunction "CRYSTAL2_10") (pintype "bidirectional"))
    )
    (net (code "81") (name "Net-(SLAVE2-DIGITAL_2)") (class "Default")
      (node (ref "M3") (pin "1") (pinfunction "1_1") (pintype "passive"))
      (node (ref "SLAVE2") (pin "4") (pinfunction "DIGITAL_2_4") (pintype "bidirectional"))
    )
    (net (code "82") (name "Net-(SLAVE2-DIGITAL_3)") (class "Default")
      (node (ref "M3") (pin "2") (pinfunction "2_2") (pintype "passive"))
      (node (ref "SLAVE2") (pin "5") (pinfunction "DIGITAL_3_5") (pintype "bidirectional"))
    )
    (net (code "83") (name "Net-(SLAVE2-DIGITAL_5)") (class "Default")
      (node (ref "M4") (pin "1") (pinfunction "1_1") (pintype "passive"))
      (node (ref "SLAVE2") (pin "11") (pinfunction "DIGITAL_5_11") (pintype "bidirectional"))
    )
    (net (code "84") (name "Net-(SLAVE2-DIGITAL_6)") (class "Default")
      (node (ref "M4") (pin "2") (pinfunction "2_2") (pintype "passive"))
      (node (ref "SLAVE2") (pin "12") (pinfunction "DIGITAL_6_12") (pintype "bidirectional"))
    )
    (net (code "85") (name "Net-(SLAVE2-DIGITAL_9(PWM))") (class "Default")
      (node (ref "P3P4") (pin "1") (pinfunction "1_1") (pintype "passive"))
      (node (ref "SLAVE2") (pin "15") (pinfunction "DIGITAL_9(PWM)_15") (pintype "bidirectional"))
    )
    (net (code "86") (name "Net-(SLAVE2-DIGITAL_10(PWM))") (class "Default")
      (node (ref "P3P4") (pin "2") (pinfunction "2_2") (pintype "passive"))
      (node (ref "SLAVE2") (pin "16") (pinfunction "DIGITAL_10(PWM)_16") (pintype "bidirectional"))
    )
    (net (code "87") (name "Net-(SLAVE2-GND)") (class "Default")
      (node (ref "J2") (pin "2") (pinfunction "2_2") (pintype "passive"))
      (node (ref "SLAVE2") (pin "8") (pinfunction "GND_8") (pintype "power_in"))
    )
    (net (code "88") (name "Net-(SLAVE3-ANALOG_0)") (class "Default")
      (node (ref "E5E6") (pin "1") (pinfunction "1_1") (pintype "passive"))
      (node (ref "SLAVE3") (pin "23") (pinfunction "ANALOG_0_23") (pintype "bidirectional"))
    )
    (net (code "89") (name "Net-(SLAVE3-ANALOG_1)") (class "Default")
      (node (ref "E5E6") (pin "2") (pinfunction "2_2") (pintype "passive"))
      (node (ref "SLAVE3") (pin "24") (pinfunction "ANALOG_1_24") (pintype "bidirectional"))
    )
    (net (code "90") (name "Net-(SLAVE3-ANALOG_2)") (class "Default")
      (node (ref "H5H6") (pin "1") (pinfunction "1_1") (pintype "passive"))
      (node (ref "SLAVE3") (pin "25") (pinfunction "ANALOG_2_25") (pintype "bidirectional"))
    )
    (net (code "91") (name "Net-(SLAVE3-ANALOG_3)") (class "Default")
      (node (ref "H5H6") (pin "2") (pinfunction "2_2") (pintype "passive"))
      (node (ref "SLAVE3") (pin "26") (pinfunction "ANALOG_3_26") (pintype "bidirectional"))
    )
    (net (code "92") (name "Net-(SLAVE3-ANALOG_4)") (class "Default")
      (node (ref "R_S8") (pin "2") (pinfunction "2_2") (pintype "passive"))
      (node (ref "SLAVE3") (pin "27") (pinfunction "ANALOG_4_27") (pintype "bidirectional"))
    )
    (net (code "93") (name "Net-(SLAVE3-ANALOG_5)") (class "Default")
      (node (ref "R_S9") (pin "2") (pinfunction "2_2") (pintype "passive"))
      (node (ref "SLAVE3") (pin "28") (pinfunction "ANALOG_5_28") (pintype "bidirectional"))
    )
    (net (code "94") (name "Net-(SLAVE3-CRYSTAL1)") (class "Default")
      (node (ref "CLKGND7") (pin "2") (pinfunction "2_2") (pintype "passive"))
      (node (ref "CLK_S3") (pin "2") (pinfunction "2_2") (pintype "passive"))
      (node (ref "SLAVE3") (pin "9") (pinfunction "CRYSTAL1_9") (pintype "bidirectional"))
    )
    (net (code "95") (name "Net-(SLAVE3-CRYSTAL2)") (class "Default")
      (node (ref "CLKGND8") (pin "2") (pinfunction "2_2") (pintype "passive"))
      (node (ref "CLK_S3") (pin "1") (pinfunction "1_1") (pintype "passive"))
      (node (ref "SLAVE3") (pin "10") (pinfunction "CRYSTAL2_10") (pintype "bidirectional"))
    )
    (net (code "96") (name "Net-(SLAVE3-DIGITAL_2)") (class "Default")
      (node (ref "M5") (pin "1") (pinfunction "1_1") (pintype "passive"))
      (node (ref "SLAVE3") (pin "4") (pinfunction "DIGITAL_2_4") (pintype "bidirectional"))
    )
    (net (code "97") (name "Net-(SLAVE3-DIGITAL_3)") (class "Default")
      (node (ref "M5") (pin "2") (pinfunction "2_2") (pintype "passive"))
      (node (ref "SLAVE3") (pin "5") (pinfunction "DIGITAL_3_5") (pintype "bidirectional"))
    )
    (net (code "98") (name "Net-(SLAVE3-DIGITAL_5)") (class "Default")
      (node (ref "M6") (pin "1") (pinfunction "1_1") (pintype "passive"))
      (node (ref "SLAVE3") (pin "11") (pinfunction "DIGITAL_5_11") (pintype "bidirectional"))
    )
    (net (code "99") (name "Net-(SLAVE3-DIGITAL_6)") (class "Default")
      (node (ref "M6") (pin "2") (pinfunction "2_2") (pintype "passive"))
      (node (ref "SLAVE3") (pin "12") (pinfunction "DIGITAL_6_12") (pintype "bidirectional"))
    )
    (net (code "100") (name "Net-(SLAVE3-DIGITAL_9(PWM))") (class "Default")
      (node (ref "P5P6") (pin "1") (pinfunction "1_1") (pintype "passive"))
      (node (ref "SLAVE3") (pin "15") (pinfunction "DIGITAL_9(PWM)_15") (pintype "bidirectional"))
    )
    (net (code "101") (name "Net-(SLAVE3-DIGITAL_10(PWM))") (class "Default")
      (node (ref "P5P6") (pin "2") (pinfunction "2_2") (pintype "passive"))
      (node (ref "SLAVE3") (pin "16") (pinfunction "DIGITAL_10(PWM)_16") (pintype "bidirectional"))
    )
    (net (code "102") (name "Net-(SLAVE3-GND)") (class "Default")
      (node (ref "J1") (pin "2") (pinfunction "2_2") (pintype "passive"))
      (node (ref "SLAVE3") (pin "8") (pinfunction "GND_8") (pintype "power_in"))
    )
    (net (code "103") (name "VCC") (class "Default")
      (node (ref "5V") (pin "1") (pinfunction "1_1") (pintype "passive"))
      (node (ref "5V") (pin "10") (pinfunction "10_10") (pintype "passive"))
      (node (ref "5V") (pin "2") (pinfunction "2_2") (pintype "passive"))
      (node (ref "5V") (pin "3") (pinfunction "3_3") (pintype "passive"))
      (node (ref "5V") (pin "4") (pinfunction "4_4") (pintype "passive"))
      (node (ref "5V") (pin "5") (pinfunction "5_5") (pintype "passive"))
      (node (ref "5V") (pin "6") (pinfunction "6_6") (pintype "passive"))
      (node (ref "5V") (pin "7") (pinfunction "7_7") (pintype "passive"))
      (node (ref "5V") (pin "8") (pinfunction "8_8") (pintype "passive"))
      (node (ref "5V") (pin "9") (pinfunction "9_9") (pintype "passive"))
      (node (ref "FRC1_VCC") (pin "2") (pinfunction "2_2") (pintype "passive"))
      (node (ref "FRC2_VCC") (pin "2") (pinfunction "2_2") (pintype "passive"))
      (node (ref "FRC3_VCC") (pin "2") (pinfunction "2_2") (pintype "passive"))
      (node (ref "I2C_1") (pin "2") (pinfunction "2_2") (pintype "passive"))
      (node (ref "I2C_2") (pin "1") (pinfunction "1_1") (pintype "passive"))
      (node (ref "LD33") (pin "IN") (pinfunction "IN_IN") (pintype "input"))
      (node (ref "POWER") (pin "1") (pinfunction "O_1") (pintype "passive"))
      (node (ref "POWER_M") (pin "2") (pinfunction "P_2") (pintype "passive"))
      (node (ref "POWER_S1") (pin "2") (pinfunction "P_2") (pintype "passive"))
      (node (ref "POWER_S2") (pin "2") (pinfunction "P_2") (pintype "passive"))
      (node (ref "POWER_S3") (pin "2") (pinfunction "P_2") (pintype "passive"))
      (node (ref "R_M") (pin "1") (pinfunction "1_1") (pintype "passive"))
      (node (ref "R_S1") (pin "1") (pinfunction "1_1") (pintype "passive"))
      (node (ref "R_S2") (pin "1") (pinfunction "1_1") (pintype "passive"))
      (node (ref "R_S3") (pin "1") (pinfunction "1_1") (pintype "passive"))
    )
    (net (code "104") (name "unconnected-(.-Pad2)") (class "Default")
      (node (ref ".") (pin "2") (pinfunction "2_2") (pintype "passive"))
    )
    (net (code "105") (name "unconnected-(.-Pad3)") (class "Default")
      (node (ref ".") (pin "3") (pinfunction "3_3") (pintype "passive"))
    )
    (net (code "106") (name "unconnected-(3V3-Pad2)") (class "Default")
      (node (ref "3V3") (pin "2") (pinfunction "2_2") (pintype "passive"))
    )
    (net (code "107") (name "unconnected-(3V3-Pad3)") (class "Default")
      (node (ref "3V3") (pin "3") (pinfunction "3_3") (pintype "passive"))
    )
    (net (code "108") (name "unconnected-(FRC_S1D-S-Pad3)") (class "Default")
      (node (ref "FRC_S1") (pin "3") (pinfunction "S_3") (pintype "passive"))
    )
    (net (code "109") (name "unconnected-(FRC_S2D-S-Pad3)") (class "Default")
      (node (ref "FRC_S2") (pin "3") (pinfunction "S_3") (pintype "passive"))
    )
    (net (code "110") (name "unconnected-(FRC_S3D-S-Pad3)") (class "Default")
      (node (ref "FRC_S3") (pin "3") (pinfunction "S_3") (pintype "passive"))
    )
    (net (code "111") (name "unconnected-(NRF24L01+-Pad8)") (class "Default")
      (node (ref "NRF24L01+") (pin "8") (pinfunction "8_8") (pintype "passive"))
    )
    (net (code "112") (name "unconnected-(POWER-S-Pad3)") (class "Default")
      (node (ref "POWER") (pin "3") (pinfunction "S_3") (pintype "passive"))
    )
    (net (code "113") (name "unconnected-(POWER_M-S-Pad3)") (class "Default")
      (node (ref "POWER_M") (pin "3") (pinfunction "S_3") (pintype "passive"))
    )
    (net (code "114") (name "unconnected-(POWER_S1-S-Pad3)") (class "Default")
      (node (ref "POWER_S1") (pin "3") (pinfunction "S_3") (pintype "passive"))
    )
    (net (code "115") (name "unconnected-(POWER_S2-S-Pad3)") (class "Default")
      (node (ref "POWER_S2") (pin "3") (pinfunction "S_3") (pintype "passive"))
    )
    (net (code "116") (name "unconnected-(POWER_S3-S-Pad3)") (class "Default")
      (node (ref "POWER_S3") (pin "3") (pinfunction "S_3") (pintype "passive"))
    )
    (net (code "117") (name "unconnected-(SLAVE1-DIGITAL_0(RX)-Pad2)") (class "Default")
      (node (ref "SLAVE1") (pin "2") (pinfunction "DIGITAL_0(RX)_2") (pintype "bidirectional"))
    )
    (net (code "118") (name "unconnected-(SLAVE1-DIGITAL_1(TX)-Pad3)") (class "Default")
      (node (ref "SLAVE1") (pin "3") (pinfunction "DIGITAL_1(TX)_3") (pintype "bidirectional"))
    )
    (net (code "119") (name "unconnected-(SLAVE1-DIGITAL_4-Pad6)") (class "Default")
      (node (ref "SLAVE1") (pin "6") (pinfunction "DIGITAL_4_6") (pintype "bidirectional"))
    )
    (net (code "120") (name "unconnected-(SLAVE1-DIGITAL_7-Pad13)") (class "Default")
      (node (ref "SLAVE1") (pin "13") (pinfunction "DIGITAL_7_13") (pintype "bidirectional"))
    )
    (net (code "121") (name "unconnected-(SLAVE1-DIGITAL_8-Pad14)") (class "Default")
      (node (ref "SLAVE1") (pin "14") (pinfunction "DIGITAL_8_14") (pintype "bidirectional"))
    )
    (net (code "122") (name "unconnected-(SLAVE2-DIGITAL_0(RX)-Pad2)") (class "Default")
      (node (ref "SLAVE2") (pin "2") (pinfunction "DIGITAL_0(RX)_2") (pintype "bidirectional"))
    )
    (net (code "123") (name "unconnected-(SLAVE2-DIGITAL_1(TX)-Pad3)") (class "Default")
      (node (ref "SLAVE2") (pin "3") (pinfunction "DIGITAL_1(TX)_3") (pintype "bidirectional"))
    )
    (net (code "124") (name "unconnected-(SLAVE2-DIGITAL_4-Pad6)") (class "Default")
      (node (ref "SLAVE2") (pin "6") (pinfunction "DIGITAL_4_6") (pintype "bidirectional"))
    )
    (net (code "125") (name "unconnected-(SLAVE2-DIGITAL_7-Pad13)") (class "Default")
      (node (ref "SLAVE2") (pin "13") (pinfunction "DIGITAL_7_13") (pintype "bidirectional"))
    )
    (net (code "126") (name "unconnected-(SLAVE2-DIGITAL_8-Pad14)") (class "Default")
      (node (ref "SLAVE2") (pin "14") (pinfunction "DIGITAL_8_14") (pintype "bidirectional"))
    )
    (net (code "127") (name "unconnected-(SLAVE3-DIGITAL_0(RX)-Pad2)") (class "Default")
      (node (ref "SLAVE3") (pin "2") (pinfunction "DIGITAL_0(RX)_2") (pintype "bidirectional"))
    )
    (net (code "128") (name "unconnected-(SLAVE3-DIGITAL_1(TX)-Pad3)") (class "Default")
      (node (ref "SLAVE3") (pin "3") (pinfunction "DIGITAL_1(TX)_3") (pintype "bidirectional"))
    )
    (net (code "129") (name "unconnected-(SLAVE3-DIGITAL_4-Pad6)") (class "Default")
      (node (ref "SLAVE3") (pin "6") (pinfunction "DIGITAL_4_6") (pintype "bidirectional"))
    )
    (net (code "130") (name "unconnected-(SLAVE3-DIGITAL_7-Pad13)") (class "Default")
      (node (ref "SLAVE3") (pin "13") (pinfunction "DIGITAL_7_13") (pintype "bidirectional"))
    )
    (net (code "131") (name "unconnected-(SLAVE3-DIGITAL_8-Pad14)") (class "Default")
      (node (ref "SLAVE3") (pin "14") (pinfunction "DIGITAL_8_14") (pintype "bidirectional"))
    )
  )
)
